# Un_51_2_old.net
KiCad netlist of a schematic drawn in EAGLE
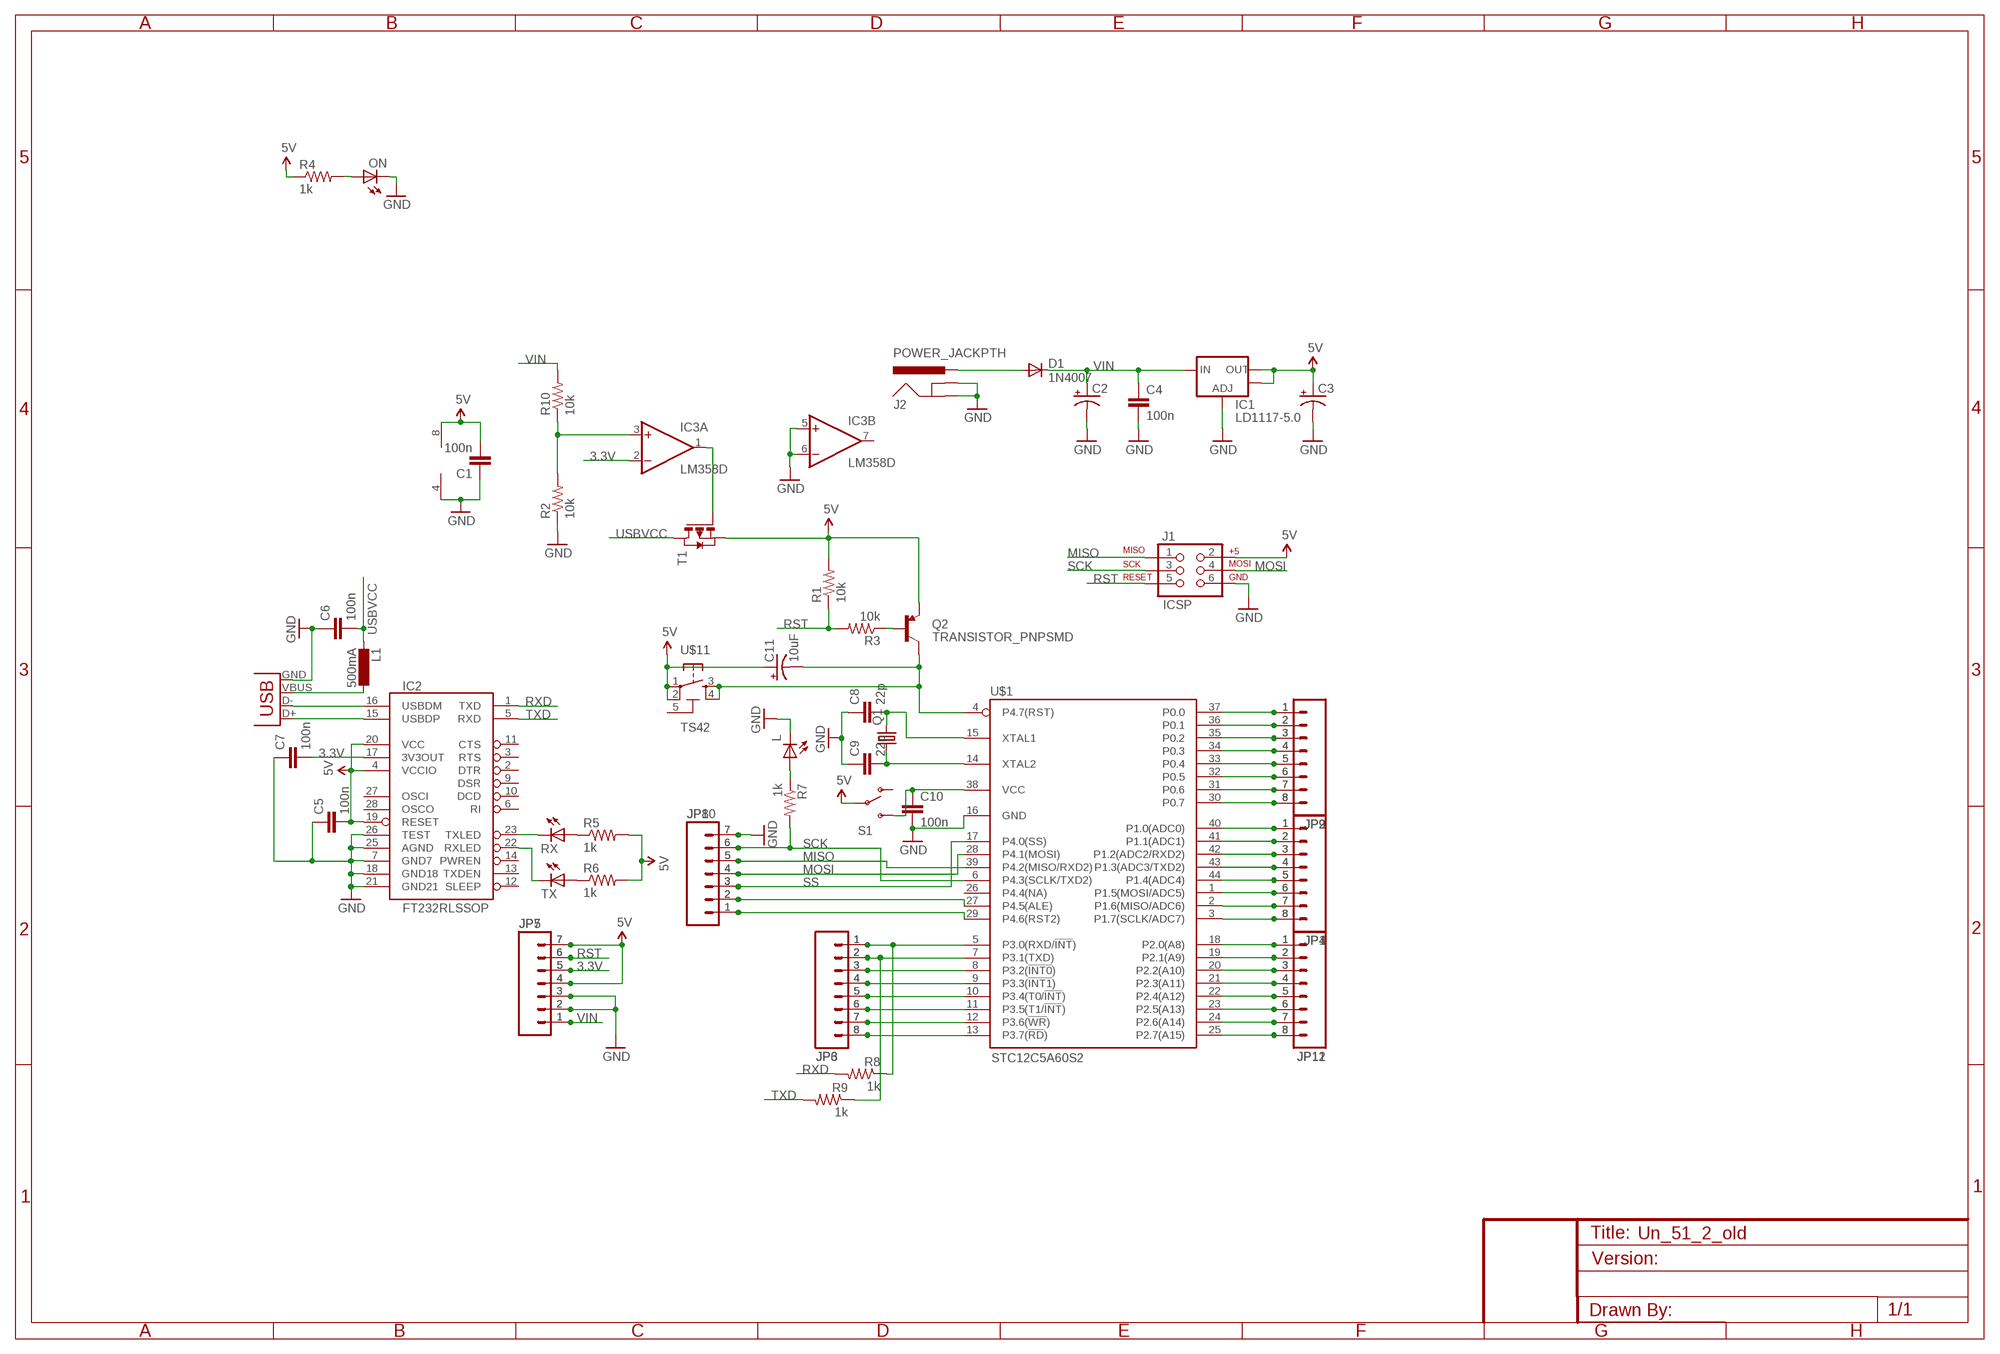
[diagram p0: schematic, sheet 1]

(export (version "E")
  (design (tool "Eeschema 10.0.6"))
  (components
    (comp (ref "C1")
      (value "100n")
      (footprint "eagle-import:0603-CAP")
      (libsource (lib "eagle-import") (part "CAP0603-CAP"))
    )
    (comp (ref "C2")
      (value "CAP_POLD")
      (footprint "eagle-import:PANASONIC_D")
      (libsource (lib "eagle-import") (part "CAP_POLD"))
    )
    (comp (ref "C3")
      (value "CAP_POLD")
      (footprint "eagle-import:PANASONIC_D")
      (libsource (lib "eagle-import") (part "CAP_POLD"))
    )
    (comp (ref "C4")
      (value "100n")
      (footprint "eagle-import:0603-CAP")
      (libsource (lib "eagle-import") (part "CAP0603-CAP"))
    )
    (comp (ref "C5")
      (value "100n")
      (footprint "eagle-import:0603-CAP")
      (libsource (lib "eagle-import") (part "CAP0603-CAP"))
    )
    (comp (ref "C6")
      (value "100n")
      (footprint "eagle-import:0603-CAP")
      (libsource (lib "eagle-import") (part "CAP0603-CAP"))
    )
    (comp (ref "C7")
      (value "100n")
      (footprint "eagle-import:0603-CAP")
      (libsource (lib "eagle-import") (part "CAP0603-CAP"))
    )
    (comp (ref "C8")
      (value "22p")
      (footprint "eagle-import:0805")
      (libsource (lib "eagle-import") (part "CAP0805"))
    )
    (comp (ref "C9")
      (value "22p")
      (footprint "eagle-import:0805")
      (libsource (lib "eagle-import") (part "CAP0805"))
    )
    (comp (ref "C10")
      (value "100n")
      (footprint "eagle-import:0603-CAP")
      (libsource (lib "eagle-import") (part "CAP0603-CAP"))
    )
    (comp (ref "C11")
      (value "10uF")
      (footprint "eagle-import:EIA3216")
      (libsource (lib "eagle-import") (part "CAP_POL1206"))
    )
    (comp (ref "D1")
      (value "1N4007")
      (footprint "eagle-import:SMB")
      (libsource (lib "eagle-import") (part "DIODE-SMB"))
    )
    (comp (ref "IC1")
      (value "LD1117-5.0")
      (footprint "eagle-import:SOT223")
      (libsource (lib "eagle-import") (part "V_REG_LM1117SOT223"))
    )
    (comp (ref "IC2")
      (value "FT232RLSSOP")
      (footprint "eagle-import:SSOP28DB")
      (libsource (lib "eagle-import") (part "FT232RLSSOP"))
    )
    (comp (ref "IC3")
      (value "LM358D")
      (footprint "eagle-import:SO08")
      (libsource (lib "eagle-import") (part "LM358D"))
    )
    (comp (ref "J1")
      (value "ICSP")
      (footprint "eagle-import:2X3")
      (libsource (lib "eagle-import") (part "AVR_SPI_PRG_6PTH"))
    )
    (comp (ref "J2")
      (value "POWER_JACKPTH")
      (footprint "eagle-import:POWER_JACK_PTH")
      (libsource (lib "eagle-import") (part "POWER_JACKPTH"))
    )
    (comp (ref "JP1")
      (value "M081X08")
      (footprint "eagle-import:1X08")
      (libsource (lib "eagle-import") (part "M081X08"))
    )
    (comp (ref "JP2")
      (value "M081X08")
      (footprint "eagle-import:1X08")
      (libsource (lib "eagle-import") (part "M081X08"))
    )
    (comp (ref "JP3")
      (value "M08")
      (footprint "eagle-import:1X08")
      (libsource (lib "eagle-import") (part "M08"))
    )
    (comp (ref "JP4")
      (value "M081X08")
      (footprint "eagle-import:1X08")
      (libsource (lib "eagle-import") (part "M081X08"))
    )
    (comp (ref "JP5")
      (value "M07")
      (footprint "eagle-import:1X07")
      (libsource (lib "eagle-import") (part "M07"))
    )
    (comp (ref "JP6")
      (value "M08")
      (footprint "eagle-import:1X08")
      (libsource (lib "eagle-import") (part "M08"))
    )
    (comp (ref "JP7")
      (value "M07")
      (footprint "eagle-import:1X07")
      (libsource (lib "eagle-import") (part "M07"))
    )
    (comp (ref "JP8")
      (value "M07")
      (footprint "eagle-import:1X07")
      (libsource (lib "eagle-import") (part "M07"))
    )
    (comp (ref "JP9")
      (value "M081X08")
      (footprint "eagle-import:1X08")
      (libsource (lib "eagle-import") (part "M081X08"))
    )
    (comp (ref "JP10")
      (value "M07")
      (footprint "eagle-import:1X07")
      (libsource (lib "eagle-import") (part "M07"))
    )
    (comp (ref "JP11")
      (value "M081X08")
      (footprint "eagle-import:1X08")
      (libsource (lib "eagle-import") (part "M081X08"))
    )
    (comp (ref "JP12")
      (value "M081X08")
      (footprint "eagle-import:1X08")
      (libsource (lib "eagle-import") (part "M081X08"))
    )
    (comp (ref "L")
      (value "LED0805")
      (footprint "eagle-import:LED-0805")
      (libsource (lib "eagle-import") (part "LED0805"))
    )
    (comp (ref "L1")
      (value "500mA")
      (footprint "eagle-import:L1812")
      (libsource (lib "eagle-import") (part "L-EUL1812"))
    )
    (comp (ref "ON")
      (value "LED0805")
      (footprint "eagle-import:LED-0805")
      (libsource (lib "eagle-import") (part "LED0805"))
    )
    (comp (ref "Q1")
      (value "CRYSTALHC49US")
      (footprint "eagle-import:HC49US")
      (libsource (lib "eagle-import") (part "CRYSTALHC49US"))
    )
    (comp (ref "Q2")
      (value "TRANSISTOR_PNPSMD")
      (footprint "eagle-import:SOT23-3")
      (libsource (lib "eagle-import") (part "TRANSISTOR_PNPSMD"))
    )
    (comp (ref "R1")
      (value "10k")
      (footprint "eagle-import:0805")
      (libsource (lib "eagle-import") (part "RESISTOR0805-RES"))
    )
    (comp (ref "R2")
      (value "10k")
      (footprint "eagle-import:0805")
      (libsource (lib "eagle-import") (part "RESISTOR0805-RES"))
    )
    (comp (ref "R3")
      (value "10k")
      (footprint "eagle-import:0805")
      (libsource (lib "eagle-import") (part "RESISTOR0805-RES"))
    )
    (comp (ref "R4")
      (value "1k")
      (footprint "eagle-import:0805")
      (libsource (lib "eagle-import") (part "RESISTOR0805-RES"))
    )
    (comp (ref "R5")
      (value "1k")
      (footprint "eagle-import:0805")
      (libsource (lib "eagle-import") (part "RESISTOR0805-RES"))
    )
    (comp (ref "R6")
      (value "1k")
      (footprint "eagle-import:0805")
      (libsource (lib "eagle-import") (part "RESISTOR0805-RES"))
    )
    (comp (ref "R7")
      (value "1k")
      (footprint "eagle-import:0805")
      (libsource (lib "eagle-import") (part "RESISTOR0805-RES"))
    )
    (comp (ref "R8")
      (value "1k")
      (footprint "eagle-import:0805")
      (libsource (lib "eagle-import") (part "RESISTOR0805-RES"))
    )
    (comp (ref "R9")
      (value "1k")
      (footprint "eagle-import:0805")
      (libsource (lib "eagle-import") (part "RESISTOR0805-RES"))
    )
    (comp (ref "R10")
      (value "10k")
      (footprint "eagle-import:0805")
      (libsource (lib "eagle-import") (part "RESISTOR0805-RES"))
    )
    (comp (ref "RX")
      (value "LED0805")
      (footprint "eagle-import:LED-0805")
      (libsource (lib "eagle-import") (part "LED0805"))
    )
    (comp (ref "S1")
      (value "SWITCH-SPST")
      (footprint "eagle-import:SWITCH-SPDT2")
      (libsource (lib "eagle-import") (part "SWITCH-SPST"))
    )
    (comp (ref "T1")
      (value "PMOSSOT23")
      (footprint "eagle-import:SOT-23")
      (libsource (lib "eagle-import") (part "PMOSSOT23"))
    )
    (comp (ref "TX")
      (value "LED0805")
      (footprint "eagle-import:LED-0805")
      (libsource (lib "eagle-import") (part "LED0805"))
    )
    (comp (ref "U$1")
      (value "STC12C5A60S2")
      (footprint "eagle-import:TQFP44")
      (libsource (lib "eagle-import") (part "STC12C5A60S2"))
    )
    (comp (ref "U$11")
      (value "TS42")
      (footprint "eagle-import:TS42")
      (libsource (lib "eagle-import") (part "TS42"))
    )
    (comp (ref "X1")
      (value "USBPTH")
      (footprint "eagle-import:USB-B-PTH")
      (libsource (lib "eagle-import") (part "USBPTH"))
    )
  )
  (nets
    (net (code "1") (name "/3.3V") (class "Default")
      (node (ref "C7") (pin "2") (pinfunction "2_2") (pintype "passive"))
      (node (ref "IC2") (pin "17") (pinfunction "3V3OUT_17") (pintype "output"))
      (node (ref "IC3") (pin "2") (pinfunction "-IN_2") (pintype "input"))
      (node (ref "JP5") (pin "5") (pinfunction "5_5") (pintype "passive"))
      (node (ref "JP7") (pin "5") (pinfunction "5_5") (pintype "passive"))
    )
    (net (code "2") (name "/MISO") (class "Default")
      (node (ref "J1") (pin "1") (pinfunction "1_1") (pintype "passive"))
      (node (ref "JP10") (pin "5") (pinfunction "5_5") (pintype "passive"))
      (node (ref "JP8") (pin "5") (pinfunction "5_5") (pintype "passive"))
      (node (ref "U$1") (pin "39") (pinfunction "P4.2(MISO/RXD2)_39") (pintype "bidirectional"))
    )
    (net (code "3") (name "/MOSI") (class "Default")
      (node (ref "J1") (pin "4") (pinfunction "4_4") (pintype "passive"))
      (node (ref "JP10") (pin "4") (pinfunction "4_4") (pintype "passive"))
      (node (ref "JP8") (pin "4") (pinfunction "4_4") (pintype "passive"))
      (node (ref "U$1") (pin "28") (pinfunction "P4.1(MOSI)_28") (pintype "bidirectional"))
    )
    (net (code "4") (name "/RST") (class "Default")
      (node (ref "J1") (pin "5") (pinfunction "5_5") (pintype "passive"))
      (node (ref "JP5") (pin "6") (pinfunction "6_6") (pintype "passive"))
      (node (ref "JP7") (pin "6") (pinfunction "6_6") (pintype "passive"))
      (node (ref "R1") (pin "1") (pinfunction "1_1") (pintype "passive"))
      (node (ref "R3") (pin "2") (pinfunction "2_2") (pintype "passive"))
    )
    (net (code "5") (name "/RXD") (class "Default")
      (node (ref "IC2") (pin "1") (pinfunction "TXD_1") (pintype "output"))
      (node (ref "R8") (pin "2") (pinfunction "2_2") (pintype "passive"))
    )
    (net (code "6") (name "/SCK") (class "Default")
      (node (ref "J1") (pin "3") (pinfunction "3_3") (pintype "passive"))
      (node (ref "JP10") (pin "6") (pinfunction "6_6") (pintype "passive"))
      (node (ref "JP8") (pin "6") (pinfunction "6_6") (pintype "passive"))
      (node (ref "R7") (pin "2") (pinfunction "2_2") (pintype "passive"))
      (node (ref "U$1") (pin "6") (pinfunction "P4.3(SCLK/TXD2)_6") (pintype "bidirectional"))
    )
    (net (code "7") (name "/SS") (class "Default")
      (node (ref "JP10") (pin "3") (pinfunction "3_3") (pintype "passive"))
      (node (ref "JP8") (pin "3") (pinfunction "3_3") (pintype "passive"))
      (node (ref "U$1") (pin "17") (pinfunction "P4.0(SS)_17") (pintype "bidirectional"))
    )
    (net (code "8") (name "/TXD") (class "Default")
      (node (ref "IC2") (pin "5") (pinfunction "RXD_5") (pintype "input"))
      (node (ref "R9") (pin "2") (pinfunction "2_2") (pintype "passive"))
    )
    (net (code "9") (name "/USBVCC") (class "Default")
      (node (ref "C6") (pin "2") (pinfunction "2_2") (pintype "passive"))
      (node (ref "L1") (pin "2") (pinfunction "2_2") (pintype "passive"))
      (node (ref "T1") (pin "1") (pinfunction "D_1") (pintype "passive"))
    )
    (net (code "10") (name "/VIN") (class "Default")
      (node (ref "C2") (pin "+") (pinfunction "+_+") (pintype "passive"))
      (node (ref "C4") (pin "1") (pinfunction "1_1") (pintype "passive"))
      (node (ref "D1") (pin "C") (pinfunction "C_C") (pintype "passive"))
      (node (ref "IC1") (pin "3") (pinfunction "IN_3") (pintype "input"))
      (node (ref "JP5") (pin "1") (pinfunction "1_1") (pintype "passive"))
      (node (ref "JP7") (pin "1") (pinfunction "1_1") (pintype "passive"))
      (node (ref "R10") (pin "2") (pinfunction "2_2") (pintype "passive"))
    )
    (net (code "11") (name "5V") (class "Default")
      (node (ref "C1") (pin "2") (pinfunction "2_2") (pintype "passive"))
      (node (ref "C11") (pin "A") (pinfunction "+_A") (pintype "passive"))
      (node (ref "C3") (pin "+") (pinfunction "+_+") (pintype "passive"))
      (node (ref "C5") (pin "2") (pinfunction "2_2") (pintype "passive"))
      (node (ref "IC1") (pin "2") (pinfunction "OUT_2") (pintype "output"))
      (node (ref "IC1") (pin "4") (pinfunction "OUT_4") (pintype "output"))
      (node (ref "IC2") (pin "19") (pinfunction "RESET_19") (pintype "input"))
      (node (ref "IC2") (pin "20") (pinfunction "VCC_20") (pintype "power_in"))
      (node (ref "IC2") (pin "4") (pinfunction "VCCIO_4") (pintype "power_in"))
      (node (ref "IC3") (pin "8") (pinfunction "V+_8") (pintype "power_in"))
      (node (ref "J1") (pin "2") (pinfunction "2_2") (pintype "passive"))
      (node (ref "JP5") (pin "4") (pinfunction "4_4") (pintype "passive"))
      (node (ref "JP5") (pin "7") (pinfunction "7_7") (pintype "passive"))
      (node (ref "JP7") (pin "4") (pinfunction "4_4") (pintype "passive"))
      (node (ref "JP7") (pin "7") (pinfunction "7_7") (pintype "passive"))
      (node (ref "Q2") (pin "2") (pinfunction "E_2") (pintype "passive"))
      (node (ref "R1") (pin "2") (pinfunction "2_2") (pintype "passive"))
      (node (ref "R4") (pin "1") (pinfunction "1_1") (pintype "passive"))
      (node (ref "R5") (pin "2") (pinfunction "2_2") (pintype "passive"))
      (node (ref "R6") (pin "2") (pinfunction "2_2") (pintype "passive"))
      (node (ref "S1") (pin "2") (pinfunction "P_2") (pintype "passive"))
      (node (ref "T1") (pin "2") (pinfunction "S_2") (pintype "passive"))
      (node (ref "U$11") (pin "1") (pinfunction "1_1") (pintype "passive"))
      (node (ref "U$11") (pin "2") (pinfunction "2_2") (pintype "passive"))
    )
    (net (code "12") (name "GND") (class "Default")
      (node (ref "C1") (pin "1") (pinfunction "1_1") (pintype "passive"))
      (node (ref "C10") (pin "2") (pinfunction "2_2") (pintype "passive"))
      (node (ref "C2") (pin "-") (pinfunction "-_-") (pintype "passive"))
      (node (ref "C3") (pin "-") (pinfunction "-_-") (pintype "passive"))
      (node (ref "C4") (pin "2") (pinfunction "2_2") (pintype "passive"))
      (node (ref "C5") (pin "1") (pinfunction "1_1") (pintype "passive"))
      (node (ref "C6") (pin "1") (pinfunction "1_1") (pintype "passive"))
      (node (ref "C7") (pin "1") (pinfunction "1_1") (pintype "passive"))
      (node (ref "C8") (pin "1") (pinfunction "1_1") (pintype "passive"))
      (node (ref "C9") (pin "1") (pinfunction "1_1") (pintype "passive"))
      (node (ref "IC1") (pin "1") (pinfunction "ADJ_1") (pintype "input"))
      (node (ref "IC2") (pin "18") (pinfunction "GND18_18") (pintype "power_in"))
      (node (ref "IC2") (pin "21") (pinfunction "GND21_21") (pintype "power_in"))
      (node (ref "IC2") (pin "25") (pinfunction "AGND_25") (pintype "power_in"))
      (node (ref "IC2") (pin "26") (pinfunction "TEST_26") (pintype "input"))
      (node (ref "IC2") (pin "7") (pinfunction "GND7_7") (pintype "power_in"))
      (node (ref "IC3") (pin "4") (pinfunction "V-_4") (pintype "power_in"))
      (node (ref "IC3") (pin "5") (pinfunction "+IN_5") (pintype "input"))
      (node (ref "IC3") (pin "6") (pinfunction "-IN_6") (pintype "input"))
      (node (ref "J1") (pin "6") (pinfunction "6_6") (pintype "passive"))
      (node (ref "J2") (pin "GND") (pinfunction "GND_GND") (pintype "bidirectional"))
      (node (ref "J2") (pin "GNDBREAK") (pinfunction "GNDBREAK_GNDBREAK") (pintype "bidirectional"))
      (node (ref "JP10") (pin "7") (pinfunction "7_7") (pintype "passive"))
      (node (ref "JP5") (pin "2") (pinfunction "2_2") (pintype "passive"))
      (node (ref "JP5") (pin "3") (pinfunction "3_3") (pintype "passive"))
      (node (ref "JP7") (pin "2") (pinfunction "2_2") (pintype "passive"))
      (node (ref "JP7") (pin "3") (pinfunction "3_3") (pintype "passive"))
      (node (ref "JP8") (pin "7") (pinfunction "7_7") (pintype "passive"))
      (node (ref "L") (pin "2") (pinfunction "C_2") (pintype "passive"))
      (node (ref "ON") (pin "2") (pinfunction "C_2") (pintype "passive"))
      (node (ref "R2") (pin "1") (pinfunction "1_1") (pintype "passive"))
      (node (ref "U$1") (pin "16") (pinfunction "GND_16") (pintype "bidirectional"))
      (node (ref "X1") (pin "GND") (pinfunction "GND_GND") (pintype "bidirectional"))
    )
    (net (code "13") (name "Net-(C11--)") (class "Default")
      (node (ref "C11") (pin "C") (pinfunction "-_C") (pintype "passive"))
      (node (ref "Q2") (pin "3") (pinfunction "C_3") (pintype "passive"))
      (node (ref "U$1") (pin "4") (pinfunction "P4.7(RST)_4") (pintype "bidirectional"))
      (node (ref "U$11") (pin "3") (pinfunction "3_3") (pintype "passive"))
      (node (ref "U$11") (pin "4") (pinfunction "4_4") (pintype "passive"))
    )
    (net (code "14") (name "Net-(D1-PadA)") (class "Default")
      (node (ref "D1") (pin "A") (pinfunction "A_A") (pintype "passive"))
      (node (ref "J2") (pin "PWR") (pinfunction "PWR_PWR") (pintype "bidirectional"))
    )
    (net (code "15") (name "Net-(IC2-RXLED)") (class "Default")
      (node (ref "IC2") (pin "22") (pinfunction "RXLED_22") (pintype "input"))
      (node (ref "TX") (pin "2") (pinfunction "C_2") (pintype "passive"))
    )
    (net (code "16") (name "Net-(IC2-TXLED)") (class "Default")
      (node (ref "IC2") (pin "23") (pinfunction "TXLED_23") (pintype "input"))
      (node (ref "RX") (pin "2") (pinfunction "C_2") (pintype "passive"))
    )
    (net (code "17") (name "Net-(IC2-USBDM)") (class "Default")
      (node (ref "IC2") (pin "16") (pinfunction "USBDM_16") (pintype "bidirectional"))
      (node (ref "X1") (pin "D-") (pinfunction "D-_D-") (pintype "bidirectional"))
    )
    (net (code "18") (name "Net-(IC2-USBDP)") (class "Default")
      (node (ref "IC2") (pin "15") (pinfunction "USBDP_15") (pintype "bidirectional"))
      (node (ref "X1") (pin "D+") (pinfunction "D+_D+") (pintype "bidirectional"))
    )
    (net (code "19") (name "Net-(IC3A-+IN)") (class "Default")
      (node (ref "IC3") (pin "3") (pinfunction "+IN_3") (pintype "input"))
      (node (ref "R10") (pin "1") (pinfunction "1_1") (pintype "passive"))
      (node (ref "R2") (pin "2") (pinfunction "2_2") (pintype "passive"))
    )
    (net (code "20") (name "Net-(IC3A-OUT)") (class "Default")
      (node (ref "IC3") (pin "1") (pinfunction "OUT_1") (pintype "output"))
      (node (ref "T1") (pin "3") (pinfunction "G_3") (pintype "passive"))
    )
    (net (code "21") (name "Net-(L-A)") (class "Default")
      (node (ref "L") (pin "1") (pinfunction "A_1") (pintype "passive"))
      (node (ref "R7") (pin "1") (pinfunction "1_1") (pintype "passive"))
    )
    (net (code "22") (name "Net-(L1-Pad1)") (class "Default")
      (node (ref "L1") (pin "1") (pinfunction "1_1") (pintype "passive"))
      (node (ref "X1") (pin "VBUS") (pinfunction "VBUS_VBUS") (pintype "bidirectional"))
    )
    (net (code "23") (name "Net-(ON-A)") (class "Default")
      (node (ref "ON") (pin "1") (pinfunction "A_1") (pintype "passive"))
      (node (ref "R4") (pin "2") (pinfunction "2_2") (pintype "passive"))
    )
    (net (code "24") (name "Net-(Q2-B)") (class "Default")
      (node (ref "Q2") (pin "1") (pinfunction "B_1") (pintype "passive"))
      (node (ref "R3") (pin "1") (pinfunction "1_1") (pintype "passive"))
    )
    (net (code "25") (name "Net-(RX-A)") (class "Default")
      (node (ref "R5") (pin "1") (pinfunction "1_1") (pintype "passive"))
      (node (ref "RX") (pin "1") (pinfunction "A_1") (pintype "passive"))
    )
    (net (code "26") (name "Net-(S1-S)") (class "Default")
      (node (ref "C10") (pin "1") (pinfunction "1_1") (pintype "passive"))
      (node (ref "S1") (pin "3") (pinfunction "S_3") (pintype "passive"))
      (node (ref "U$1") (pin "38") (pinfunction "VCC_38") (pintype "bidirectional"))
    )
    (net (code "27") (name "Net-(TX-A)") (class "Default")
      (node (ref "R6") (pin "1") (pinfunction "1_1") (pintype "passive"))
      (node (ref "TX") (pin "1") (pinfunction "A_1") (pintype "passive"))
    )
    (net (code "28") (name "Net-(U$1-P0.0)") (class "Default")
      (node (ref "JP2") (pin "1") (pinfunction "1_1") (pintype "passive"))
      (node (ref "JP9") (pin "1") (pinfunction "1_1") (pintype "passive"))
      (node (ref "U$1") (pin "37") (pinfunction "P0.0_37") (pintype "bidirectional"))
    )
    (net (code "29") (name "Net-(U$1-P0.1)") (class "Default")
      (node (ref "JP2") (pin "2") (pinfunction "2_2") (pintype "passive"))
      (node (ref "JP9") (pin "2") (pinfunction "2_2") (pintype "passive"))
      (node (ref "U$1") (pin "36") (pinfunction "P0.1_36") (pintype "bidirectional"))
    )
    (net (code "30") (name "Net-(U$1-P0.2)") (class "Default")
      (node (ref "JP2") (pin "3") (pinfunction "3_3") (pintype "passive"))
      (node (ref "JP9") (pin "3") (pinfunction "3_3") (pintype "passive"))
      (node (ref "U$1") (pin "35") (pinfunction "P0.2_35") (pintype "bidirectional"))
    )
    (net (code "31") (name "Net-(U$1-P0.3)") (class "Default")
      (node (ref "JP2") (pin "4") (pinfunction "4_4") (pintype "passive"))
      (node (ref "JP9") (pin "4") (pinfunction "4_4") (pintype "passive"))
      (node (ref "U$1") (pin "34") (pinfunction "P0.3_34") (pintype "bidirectional"))
    )
    (net (code "32") (name "Net-(U$1-P0.4)") (class "Default")
      (node (ref "JP2") (pin "5") (pinfunction "5_5") (pintype "passive"))
      (node (ref "JP9") (pin "5") (pinfunction "5_5") (pintype "passive"))
      (node (ref "U$1") (pin "33") (pinfunction "P0.4_33") (pintype "bidirectional"))
    )
    (net (code "33") (name "Net-(U$1-P0.5)") (class "Default")
      (node (ref "JP2") (pin "6") (pinfunction "6_6") (pintype "passive"))
      (node (ref "JP9") (pin "6") (pinfunction "6_6") (pintype "passive"))
      (node (ref "U$1") (pin "32") (pinfunction "P0.5_32") (pintype "bidirectional"))
    )
    (net (code "34") (name "Net-(U$1-P0.6)") (class "Default")
      (node (ref "JP2") (pin "7") (pinfunction "7_7") (pintype "passive"))
      (node (ref "JP9") (pin "7") (pinfunction "7_7") (pintype "passive"))
      (node (ref "U$1") (pin "31") (pinfunction "P0.6_31") (pintype "bidirectional"))
    )
    (net (code "35") (name "Net-(U$1-P0.7)") (class "Default")
      (node (ref "JP2") (pin "8") (pinfunction "8_8") (pintype "passive"))
      (node (ref "JP9") (pin "8") (pinfunction "8_8") (pintype "passive"))
      (node (ref "U$1") (pin "30") (pinfunction "P0.7_30") (pintype "bidirectional"))
    )
    (net (code "36") (name "Net-(U$1-P1.0(ADC0))") (class "Default")
      (node (ref "JP1") (pin "1") (pinfunction "1_1") (pintype "passive"))
      (node (ref "JP4") (pin "1") (pinfunction "1_1") (pintype "passive"))
      (node (ref "U$1") (pin "40") (pinfunction "P1.0(ADC0)_40") (pintype "bidirectional"))
    )
    (net (code "37") (name "Net-(U$1-P1.1(ADC1))") (class "Default")
      (node (ref "JP1") (pin "2") (pinfunction "2_2") (pintype "passive"))
      (node (ref "JP4") (pin "2") (pinfunction "2_2") (pintype "passive"))
      (node (ref "U$1") (pin "41") (pinfunction "P1.1(ADC1)_41") (pintype "bidirectional"))
    )
    (net (code "38") (name "Net-(U$1-P1.2(ADC2{slash}RXD2))") (class "Default")
      (node (ref "JP1") (pin "3") (pinfunction "3_3") (pintype "passive"))
      (node (ref "JP4") (pin "3") (pinfunction "3_3") (pintype "passive"))
      (node (ref "U$1") (pin "42") (pinfunction "P1.2(ADC2/RXD2)_42") (pintype "bidirectional"))
    )
    (net (code "39") (name "Net-(U$1-P1.3(ADC3{slash}TXD2))") (class "Default")
      (node (ref "JP1") (pin "4") (pinfunction "4_4") (pintype "passive"))
      (node (ref "JP4") (pin "4") (pinfunction "4_4") (pintype "passive"))
      (node (ref "U$1") (pin "43") (pinfunction "P1.3(ADC3/TXD2)_43") (pintype "bidirectional"))
    )
    (net (code "40") (name "Net-(U$1-P1.4(ADC4))") (class "Default")
      (node (ref "JP1") (pin "5") (pinfunction "5_5") (pintype "passive"))
      (node (ref "JP4") (pin "5") (pinfunction "5_5") (pintype "passive"))
      (node (ref "U$1") (pin "44") (pinfunction "P1.4(ADC4)_44") (pintype "bidirectional"))
    )
    (net (code "41") (name "Net-(U$1-P1.5(MOSI{slash}ADC5))") (class "Default")
      (node (ref "JP1") (pin "6") (pinfunction "6_6") (pintype "passive"))
      (node (ref "JP4") (pin "6") (pinfunction "6_6") (pintype "passive"))
      (node (ref "U$1") (pin "1") (pinfunction "P1.5(MOSI/ADC5)_1") (pintype "bidirectional"))
    )
    (net (code "42") (name "Net-(U$1-P1.6(MISO{slash}ADC6))") (class "Default")
      (node (ref "JP1") (pin "7") (pinfunction "7_7") (pintype "passive"))
      (node (ref "JP4") (pin "7") (pinfunction "7_7") (pintype "passive"))
      (node (ref "U$1") (pin "2") (pinfunction "P1.6(MISO/ADC6)_2") (pintype "bidirectional"))
    )
    (net (code "43") (name "Net-(U$1-P1.7(SCLK{slash}ADC7))") (class "Default")
      (node (ref "JP1") (pin "8") (pinfunction "8_8") (pintype "passive"))
      (node (ref "JP4") (pin "8") (pinfunction "8_8") (pintype "passive"))
      (node (ref "U$1") (pin "3") (pinfunction "P1.7(SCLK/ADC7)_3") (pintype "bidirectional"))
    )
    (net (code "44") (name "Net-(U$1-P2.0(A8))") (class "Default")
      (node (ref "JP11") (pin "1") (pinfunction "1_1") (pintype "passive"))
      (node (ref "JP12") (pin "1") (pinfunction "1_1") (pintype "passive"))
      (node (ref "U$1") (pin "18") (pinfunction "P2.0(A8)_18") (pintype "bidirectional"))
    )
    (net (code "45") (name "Net-(U$1-P2.1(A9))") (class "Default")
      (node (ref "JP11") (pin "2") (pinfunction "2_2") (pintype "passive"))
      (node (ref "JP12") (pin "2") (pinfunction "2_2") (pintype "passive"))
      (node (ref "U$1") (pin "19") (pinfunction "P2.1(A9)_19") (pintype "bidirectional"))
    )
    (net (code "46") (name "Net-(U$1-P2.2(A10))") (class "Default")
      (node (ref "JP11") (pin "3") (pinfunction "3_3") (pintype "passive"))
      (node (ref "JP12") (pin "3") (pinfunction "3_3") (pintype "passive"))
      (node (ref "U$1") (pin "20") (pinfunction "P2.2(A10)_20") (pintype "bidirectional"))
    )
    (net (code "47") (name "Net-(U$1-P2.3(A11))") (class "Default")
      (node (ref "JP11") (pin "4") (pinfunction "4_4") (pintype "passive"))
      (node (ref "JP12") (pin "4") (pinfunction "4_4") (pintype "passive"))
      (node (ref "U$1") (pin "21") (pinfunction "P2.3(A11)_21") (pintype "bidirectional"))
    )
    (net (code "48") (name "Net-(U$1-P2.4(A12))") (class "Default")
      (node (ref "JP11") (pin "5") (pinfunction "5_5") (pintype "passive"))
      (node (ref "JP12") (pin "5") (pinfunction "5_5") (pintype "passive"))
      (node (ref "U$1") (pin "22") (pinfunction "P2.4(A12)_22") (pintype "bidirectional"))
    )
    (net (code "49") (name "Net-(U$1-P2.5(A13))") (class "Default")
      (node (ref "JP11") (pin "6") (pinfunction "6_6") (pintype "passive"))
      (node (ref "JP12") (pin "6") (pinfunction "6_6") (pintype "passive"))
      (node (ref "U$1") (pin "23") (pinfunction "P2.5(A13)_23") (pintype "bidirectional"))
    )
    (net (code "50") (name "Net-(U$1-P2.6(A14))") (class "Default")
      (node (ref "JP11") (pin "7") (pinfunction "7_7") (pintype "passive"))
      (node (ref "JP12") (pin "7") (pinfunction "7_7") (pintype "passive"))
      (node (ref "U$1") (pin "24") (pinfunction "P2.6(A14)_24") (pintype "bidirectional"))
    )
    (net (code "51") (name "Net-(U$1-P2.7(A15))") (class "Default")
      (node (ref "JP11") (pin "8") (pinfunction "8_8") (pintype "passive"))
      (node (ref "JP12") (pin "8") (pinfunction "8_8") (pintype "passive"))
      (node (ref "U$1") (pin "25") (pinfunction "P2.7(A15)_25") (pintype "bidirectional"))
    )
    (net (code "52") (name "Net-(U$1-P3.0(RXD{slash}~{INT}))") (class "Default")
      (node (ref "JP3") (pin "1") (pinfunction "1_1") (pintype "passive"))
      (node (ref "JP6") (pin "1") (pinfunction "1_1") (pintype "passive"))
      (node (ref "R8") (pin "1") (pinfunction "1_1") (pintype "passive"))
      (node (ref "U$1") (pin "5") (pinfunction "P3.0(RXD/~{INT})_5") (pintype "bidirectional"))
    )
    (net (code "53") (name "Net-(U$1-P3.1(TXD))") (class "Default")
      (node (ref "JP3") (pin "2") (pinfunction "2_2") (pintype "passive"))
      (node (ref "JP6") (pin "2") (pinfunction "2_2") (pintype "passive"))
      (node (ref "R9") (pin "1") (pinfunction "1_1") (pintype "passive"))
      (node (ref "U$1") (pin "7") (pinfunction "P3.1(TXD)_7") (pintype "bidirectional"))
    )
    (net (code "54") (name "Net-(U$1-P3.2(~{INT0}))") (class "Default")
      (node (ref "JP3") (pin "3") (pinfunction "3_3") (pintype "passive"))
      (node (ref "JP6") (pin "3") (pinfunction "3_3") (pintype "passive"))
      (node (ref "U$1") (pin "8") (pinfunction "P3.2(~{INT0})_8") (pintype "bidirectional"))
    )
    (net (code "55") (name "Net-(U$1-P3.3(~{INT1}))") (class "Default")
      (node (ref "JP3") (pin "4") (pinfunction "4_4") (pintype "passive"))
      (node (ref "JP6") (pin "4") (pinfunction "4_4") (pintype "passive"))
      (node (ref "U$1") (pin "9") (pinfunction "P3.3(~{INT1})_9") (pintype "bidirectional"))
    )
    (net (code "56") (name "Net-(U$1-P3.4(T0{slash}~{INT}))") (class "Default")
      (node (ref "JP3") (pin "5") (pinfunction "5_5") (pintype "passive"))
      (node (ref "JP6") (pin "5") (pinfunction "5_5") (pintype "passive"))
      (node (ref "U$1") (pin "10") (pinfunction "P3.4(T0/~{INT})_10") (pintype "bidirectional"))
    )
    (net (code "57") (name "Net-(U$1-P3.5(T1{slash}~{INT}))") (class "Default")
      (node (ref "JP3") (pin "6") (pinfunction "6_6") (pintype "passive"))
      (node (ref "JP6") (pin "6") (pinfunction "6_6") (pintype "passive"))
      (node (ref "U$1") (pin "11") (pinfunction "P3.5(T1/~{INT})_11") (pintype "bidirectional"))
    )
    (net (code "58") (name "Net-(U$1-P3.6(~{WR}))") (class "Default")
      (node (ref "JP3") (pin "7") (pinfunction "7_7") (pintype "passive"))
      (node (ref "JP6") (pin "7") (pinfunction "7_7") (pintype "passive"))
      (node (ref "U$1") (pin "12") (pinfunction "P3.6(~{WR})_12") (pintype "bidirectional"))
    )
    (net (code "59") (name "Net-(U$1-P3.7(~{RD}))") (class "Default")
      (node (ref "JP3") (pin "8") (pinfunction "8_8") (pintype "passive"))
      (node (ref "JP6") (pin "8") (pinfunction "8_8") (pintype "passive"))
      (node (ref "U$1") (pin "13") (pinfunction "P3.7(~{RD})_13") (pintype "bidirectional"))
    )
    (net (code "60") (name "Net-(U$1-P4.5(ALE))") (class "Default")
      (node (ref "JP10") (pin "2") (pinfunction "2_2") (pintype "passive"))
      (node (ref "JP8") (pin "2") (pinfunction "2_2") (pintype "passive"))
      (node (ref "U$1") (pin "27") (pinfunction "P4.5(ALE)_27") (pintype "bidirectional"))
    )
    (net (code "61") (name "Net-(U$1-P4.6(RST2))") (class "Default")
      (node (ref "JP10") (pin "1") (pinfunction "1_1") (pintype "passive"))
      (node (ref "JP8") (pin "1") (pinfunction "1_1") (pintype "passive"))
      (node (ref "U$1") (pin "29") (pinfunction "P4.6(RST2)_29") (pintype "bidirectional"))
    )
    (net (code "62") (name "Net-(U$1-XTAL1)") (class "Default")
      (node (ref "C8") (pin "2") (pinfunction "2_2") (pintype "passive"))
      (node (ref "Q1") (pin "2") (pinfunction "2_2") (pintype "passive"))
      (node (ref "U$1") (pin "15") (pinfunction "XTAL1_15") (pintype "bidirectional"))
    )
    (net (code "63") (name "Net-(U$1-XTAL2)") (class "Default")
      (node (ref "C9") (pin "2") (pinfunction "2_2") (pintype "passive"))
      (node (ref "Q1") (pin "1") (pinfunction "1_1") (pintype "passive"))
      (node (ref "U$1") (pin "14") (pinfunction "XTAL2_14") (pintype "bidirectional"))
    )
    (net (code "64") (name "unconnected-(IC2-CTS-Pad11)") (class "Default")
      (node (ref "IC2") (pin "11") (pinfunction "CTS_11") (pintype "input"))
    )
    (net (code "65") (name "unconnected-(IC2-DCD-Pad10)") (class "Default")
      (node (ref "IC2") (pin "10") (pinfunction "DCD_10") (pintype "input"))
    )
    (net (code "66") (name "unconnected-(IC2-DSR-Pad9)") (class "Default")
      (node (ref "IC2") (pin "9") (pinfunction "DSR_9") (pintype "input"))
    )
    (net (code "67") (name "unconnected-(IC2-DTR-Pad2)") (class "Default")
      (node (ref "IC2") (pin "2") (pinfunction "DTR_2") (pintype "output"))
    )
    (net (code "68") (name "unconnected-(IC2-OSCI-Pad27)") (class "Default")
      (node (ref "IC2") (pin "27") (pinfunction "OSCI_27") (pintype "input"))
    )
    (net (code "69") (name "unconnected-(IC2-OSCO-Pad28)") (class "Default")
      (node (ref "IC2") (pin "28") (pinfunction "OSCO_28") (pintype "output"))
    )
    (net (code "70") (name "unconnected-(IC2-PWREN-Pad14)") (class "Default")
      (node (ref "IC2") (pin "14") (pinfunction "PWREN_14") (pintype "input"))
    )
    (net (code "71") (name "unconnected-(IC2-RI-Pad6)") (class "Default")
      (node (ref "IC2") (pin "6") (pinfunction "RI_6") (pintype "input"))
    )
    (net (code "72") (name "unconnected-(IC2-RTS-Pad3)") (class "Default")
      (node (ref "IC2") (pin "3") (pinfunction "RTS_3") (pintype "output"))
    )
    (net (code "73") (name "unconnected-(IC2-SLEEP-Pad12)") (class "Default")
      (node (ref "IC2") (pin "12") (pinfunction "SLEEP_12") (pintype "input"))
    )
    (net (code "74") (name "unconnected-(IC2-TXDEN-Pad13)") (class "Default")
      (node (ref "IC2") (pin "13") (pinfunction "TXDEN_13") (pintype "input"))
    )
    (net (code "75") (name "unconnected-(IC3B-OUT-Pad7)") (class "Default")
      (node (ref "IC3") (pin "7") (pinfunction "OUT_7") (pintype "output"))
    )
    (net (code "76") (name "unconnected-(S1-O-Pad1)") (class "Default")
      (node (ref "S1") (pin "1") (pinfunction "O_1") (pintype "passive"))
    )
    (net (code "77") (name "unconnected-(U$1-P4.4(NA)-Pad26)") (class "Default")
      (node (ref "U$1") (pin "26") (pinfunction "P4.4(NA)_26") (pintype "bidirectional"))
    )
    (net (code "78") (name "unconnected-(U$11-Pad5)") (class "Default")
      (node (ref "U$11") (pin "5") (pinfunction "5_5") (pintype "passive"))
    )
  )
)
